# fuente2_-_copia.net
KiCad netlist of a schematic drawn in EAGLE
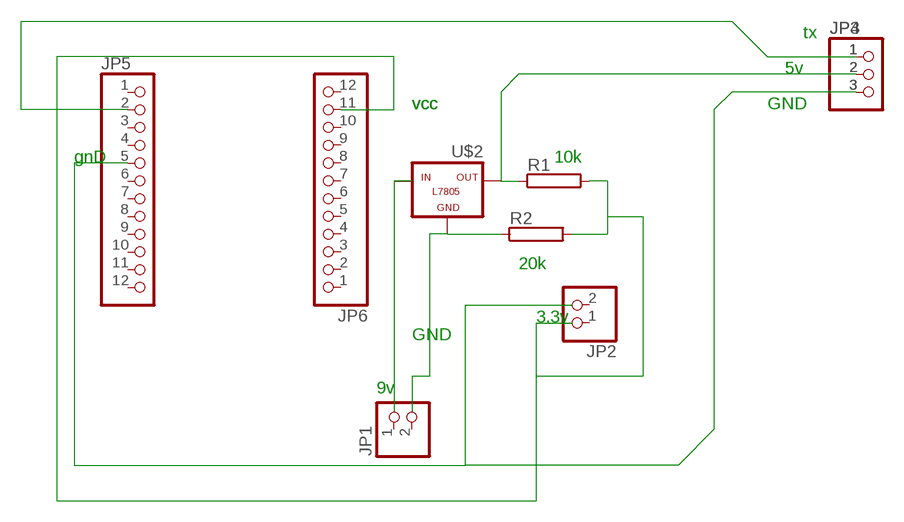
[diagram p0: schematic, sheet 1]

(export (version "E")
  (design (tool "Eeschema 10.0.6"))
  (components
    (comp (ref "JP1")
      (value "PINHD-1X2")
      (footprint "eagle-import:1X02")
      (libsource (lib "eagle-import") (part "PINHD-1X2"))
    )
    (comp (ref "JP2")
      (value "PINHD-1X2")
      (footprint "eagle-import:1X02")
      (libsource (lib "eagle-import") (part "PINHD-1X2"))
    )
    (comp (ref "JP3")
      (value "PINHD-1X3")
      (footprint "eagle-import:1X03")
      (libsource (lib "eagle-import") (part "PINHD-1X3"))
    )
    (comp (ref "JP4")
      (value "PINHD-1X3")
      (footprint "eagle-import:1X03")
      (libsource (lib "eagle-import") (part "PINHD-1X3"))
    )
    (comp (ref "JP5")
      (value "PINHD-1X12")
      (footprint "eagle-import:1X12")
      (libsource (lib "eagle-import") (part "PINHD-1X12"))
    )
    (comp (ref "JP6")
      (value "PINHD-1X12")
      (footprint "eagle-import:1X12")
      (libsource (lib "eagle-import") (part "PINHD-1X12"))
    )
    (comp (ref "R1")
      (value "RCA4050")
      (footprint "eagle-import:CA4050")
      (libsource (lib "eagle-import") (part "RCA4050"))
    )
    (comp (ref "R2")
      (value "RCA4050")
      (footprint "eagle-import:CA4050")
      (libsource (lib "eagle-import") (part "RCA4050"))
    )
    (comp (ref "U$2")
      (value "-L7805")
      (footprint "eagle-import:L7805")
      (libsource (lib "eagle-import") (part "-L7805"))
    )
  )
  (nets
    (net (code "1") (name "Net-(JP3-Pad1)") (class "Default")
      (node (ref "JP3") (pin "1") (pinfunction "1_1") (pintype "passive"))
      (node (ref "JP4") (pin "1") (pinfunction "1_1") (pintype "passive"))
      (node (ref "JP5") (pin "2") (pinfunction "2_2") (pintype "passive"))
    )
    (net (code "2") (name "Net-(JP3-Pad2)") (class "Default")
      (node (ref "JP3") (pin "2") (pinfunction "2_2") (pintype "passive"))
      (node (ref "JP4") (pin "2") (pinfunction "2_2") (pintype "passive"))
      (node (ref "R1") (pin "1") (pinfunction "1_1") (pintype "passive"))
      (node (ref "U$2") (pin "OUT") (pinfunction "OUT_OUT") (pintype "passive"))
    )
    (net (code "3") (name "Net-(JP3-Pad3)") (class "Default")
      (node (ref "JP3") (pin "3") (pinfunction "3_3") (pintype "passive"))
      (node (ref "JP4") (pin "3") (pinfunction "3_3") (pintype "passive"))
      (node (ref "JP5") (pin "5") (pinfunction "5_5") (pintype "passive"))
    )
    (net (code "4") (name "Net-(JP6-Pad11)") (class "Default")
      (node (ref "JP6") (pin "11") (pinfunction "11_11") (pintype "passive"))
      (node (ref "R1") (pin "2") (pinfunction "2_2") (pintype "passive"))
      (node (ref "R2") (pin "2") (pinfunction "2_2") (pintype "passive"))
    )
    (net (code "5") (name "Net-(R2-Pad1)") (class "Default")
      (node (ref "R2") (pin "1") (pinfunction "1_1") (pintype "passive"))
      (node (ref "U$2") (pin "GND") (pinfunction "GND_GND") (pintype "input"))
    )
    (net (code "6") (name "unconnected-(JP1-Pad1)") (class "Default")
      (node (ref "JP1") (pin "1") (pinfunction "1_1") (pintype "passive"))
    )
    (net (code "7") (name "unconnected-(JP1-Pad2)") (class "Default")
      (node (ref "JP1") (pin "2") (pinfunction "2_2") (pintype "passive"))
    )
    (net (code "8") (name "unconnected-(JP2-Pad1)") (class "Default")
      (node (ref "JP2") (pin "1") (pinfunction "1_1") (pintype "passive"))
    )
    (net (code "9") (name "unconnected-(JP2-Pad2)") (class "Default")
      (node (ref "JP2") (pin "2") (pinfunction "2_2") (pintype "passive"))
    )
    (net (code "10") (name "unconnected-(JP5-Pad1)") (class "Default")
      (node (ref "JP5") (pin "1") (pinfunction "1_1") (pintype "passive"))
    )
    (net (code "11") (name "unconnected-(JP5-Pad3)") (class "Default")
      (node (ref "JP5") (pin "3") (pinfunction "3_3") (pintype "passive"))
    )
    (net (code "12") (name "unconnected-(JP5-Pad4)") (class "Default")
      (node (ref "JP5") (pin "4") (pinfunction "4_4") (pintype "passive"))
    )
    (net (code "13") (name "unconnected-(JP5-Pad6)") (class "Default")
      (node (ref "JP5") (pin "6") (pinfunction "6_6") (pintype "passive"))
    )
    (net (code "14") (name "unconnected-(JP5-Pad7)") (class "Default")
      (node (ref "JP5") (pin "7") (pinfunction "7_7") (pintype "passive"))
    )
    (net (code "15") (name "unconnected-(JP5-Pad8)") (class "Default")
      (node (ref "JP5") (pin "8") (pinfunction "8_8") (pintype "passive"))
    )
    (net (code "16") (name "unconnected-(JP5-Pad9)") (class "Default")
      (node (ref "JP5") (pin "9") (pinfunction "9_9") (pintype "passive"))
    )
    (net (code "17") (name "unconnected-(JP5-Pad10)") (class "Default")
      (node (ref "JP5") (pin "10") (pinfunction "10_10") (pintype "passive"))
    )
    (net (code "18") (name "unconnected-(JP5-Pad11)") (class "Default")
      (node (ref "JP5") (pin "11") (pinfunction "11_11") (pintype "passive"))
    )
    (net (code "19") (name "unconnected-(JP5-Pad12)") (class "Default")
      (node (ref "JP5") (pin "12") (pinfunction "12_12") (pintype "passive"))
    )
    (net (code "20") (name "unconnected-(JP6-Pad1)") (class "Default")
      (node (ref "JP6") (pin "1") (pinfunction "1_1") (pintype "passive"))
    )
    (net (code "21") (name "unconnected-(JP6-Pad2)") (class "Default")
      (node (ref "JP6") (pin "2") (pinfunction "2_2") (pintype "passive"))
    )
    (net (code "22") (name "unconnected-(JP6-Pad3)") (class "Default")
      (node (ref "JP6") (pin "3") (pinfunction "3_3") (pintype "passive"))
    )
    (net (code "23") (name "unconnected-(JP6-Pad4)") (class "Default")
      (node (ref "JP6") (pin "4") (pinfunction "4_4") (pintype "passive"))
    )
    (net (code "24") (name "unconnected-(JP6-Pad5)") (class "Default")
      (node (ref "JP6") (pin "5") (pinfunction "5_5") (pintype "passive"))
    )
    (net (code "25") (name "unconnected-(JP6-Pad6)") (class "Default")
      (node (ref "JP6") (pin "6") (pinfunction "6_6") (pintype "passive"))
    )
    (net (code "26") (name "unconnected-(JP6-Pad7)") (class "Default")
      (node (ref "JP6") (pin "7") (pinfunction "7_7") (pintype "passive"))
    )
    (net (code "27") (name "unconnected-(JP6-Pad8)") (class "Default")
      (node (ref "JP6") (pin "8") (pinfunction "8_8") (pintype "passive"))
    )
    (net (code "28") (name "unconnected-(JP6-Pad9)") (class "Default")
      (node (ref "JP6") (pin "9") (pinfunction "9_9") (pintype "passive"))
    )
    (net (code "29") (name "unconnected-(JP6-Pad10)") (class "Default")
      (node (ref "JP6") (pin "10") (pinfunction "10_10") (pintype "passive"))
    )
    (net (code "30") (name "unconnected-(JP6-Pad12)") (class "Default")
      (node (ref "JP6") (pin "12") (pinfunction "12_12") (pintype "passive"))
    )
    (net (code "31") (name "unconnected-(U$2-PadIN)") (class "Default")
      (node (ref "U$2") (pin "IN") (pinfunction "IN_IN") (pintype "input"))
    )
  )
)
